# 1050a.net
KiCad netlist of a schematic drawn in Altium Designer
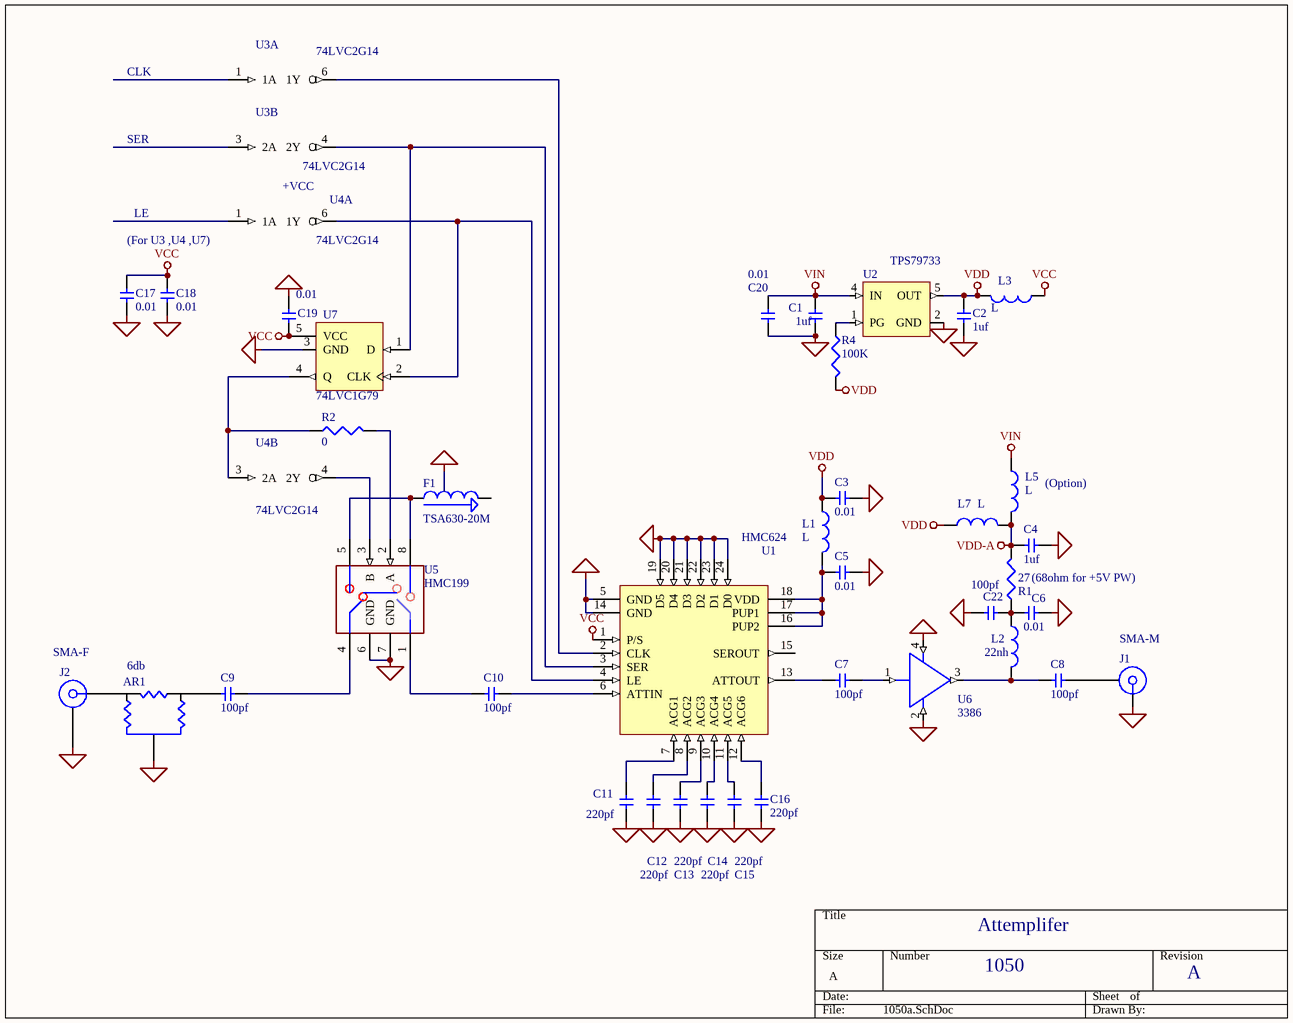
[diagram p0: 1050a.SchDoc]

(export (version "E")
  (design (tool "Eeschema 10.0.6"))
  (components
    (comp (ref "AR1") (value "6db") (libsource (lib "Project") (part "ATTN")))
    (comp (ref "C1") (value "1uf") (libsource (lib "Custom") (part "C")))
    (comp (ref "C2") (value "1uf") (libsource (lib "Custom") (part "C")))
    (comp (ref "C3") (value "0.01") (libsource (lib "Custom") (part "C")))
    (comp (ref "C4") (value "1uf") (libsource (lib "Custom") (part "C")))
    (comp (ref "C5") (value "0.01") (libsource (lib "Custom") (part "C")))
    (comp (ref "C6") (value "0.01") (libsource (lib "Custom") (part "C")))
    (comp (ref "C7") (value "100pf") (libsource (lib "Custom") (part "C")))
    (comp (ref "C8") (value "100pf") (libsource (lib "Custom") (part "C")))
    (comp (ref "C9") (value "100pf") (libsource (lib "Custom") (part "C")))
    (comp (ref "C10") (value "100pf") (libsource (lib "Custom") (part "C")))
    (comp (ref "C11") (value "220pf") (libsource (lib "Custom") (part "C")))
    (comp (ref "C12") (value "220pf") (libsource (lib "Custom") (part "C")))
    (comp (ref "C13") (value "220pf") (libsource (lib "Custom") (part "C")))
    (comp (ref "C14") (value "220pf") (libsource (lib "Custom") (part "C")))
    (comp (ref "C15") (value "220pf") (libsource (lib "Custom") (part "C")))
    (comp (ref "C16") (value "220pf") (libsource (lib "Custom") (part "C")))
    (comp (ref "C17") (value "0.01") (libsource (lib "Custom") (part "C")))
    (comp (ref "C18") (value "0.01") (libsource (lib "Custom") (part "C")))
    (comp (ref "C19") (value "0.01") (libsource (lib "Custom") (part "C")))
    (comp (ref "C20") (value "0.01") (libsource (lib "Custom") (part "C")))
    (comp (ref "C22") (value "100pf") (libsource (lib "Custom") (part "C")))
    (comp (ref "F1") (value "TSA630-20M") (libsource (lib "DDEVICE") (part "INDUCTOR VAR")))
    (comp (ref "J1") (value "SMA-M") (libsource (lib "DDEVICE") (part "BNC")))
    (comp (ref "J2") (value "SMA-F") (libsource (lib "DDEVICE") (part "BNC")))
    (comp (ref "L1") (value "L") (description "Chip Inductors") (libsource (lib "Custom") (part "L")))
    (comp (ref "L2") (value "22nh") (description "Chip Inductors") (libsource (lib "Custom") (part "L")))
    (comp (ref "L3")
      (value "L")
      (footprint "1008HS")
      (description "Chip Inductors")
      (libsource (lib "Custom") (part "L"))
    )
    (comp (ref "L5")
      (value "L")
      (footprint "1008HS")
      (description "Chip Inductors")
      (libsource (lib "Custom") (part "L"))
    )
    (comp (ref "L7")
      (value "L")
      (footprint "1008HS")
      (description "Chip Inductors")
      (libsource (lib "Custom") (part "L"))
    )
    (comp (ref "R1") (value "27") (libsource (lib "DDEVICE") (part "R")))
    (comp (ref "R2") (value "0") (libsource (lib "DDEVICE") (part "R")))
    (comp (ref "R4") (value "100K") (libsource (lib "DDEVICE") (part "R")))
    (comp (ref "U1") (value "HMC624") (libsource (lib "HITTICE") (part "HMC624")))
    (comp (ref "U2") (value "TPS79733") (libsource (lib "Project") (part "tps79733")))
    (comp (ref "U3") (value "74LVC2G14") (libsource (lib "FAIRCHILD") (part "74LVC2G14")))
    (comp (ref "U4") (value "74LVC2G14") (libsource (lib "FAIRCHILD") (part "74LVC2G14")))
    (comp (ref "U5") (value "HMC199") (libsource (lib "HITTICE") (part "hmc199")))
    (comp (ref "U6") (value "3386") (libsource (lib "Project") (part "MAR-4")))
    (comp (ref "U7") (value "74LVC1G79") (libsource (lib "TI Logic Flip-Flop") (part "74LVC1G79")))
  )
  (nets
    (net (code "1") (name "GND") (class "Default")
      (node (ref "AR1") (pin "2") (pinfunction "2_2") (pintype "passive"))
      (node (ref "C1") (pin "2") (pinfunction "2_2") (pintype "passive"))
      (node (ref "C11") (pin "2") (pinfunction "2_2") (pintype "passive"))
      (node (ref "C12") (pin "2") (pinfunction "2_2") (pintype "passive"))
      (node (ref "C13") (pin "2") (pinfunction "2_2") (pintype "passive"))
      (node (ref "C14") (pin "2") (pinfunction "2_2") (pintype "passive"))
      (node (ref "C15") (pin "2") (pinfunction "2_2") (pintype "passive"))
      (node (ref "C16") (pin "2") (pinfunction "2_2") (pintype "passive"))
      (node (ref "C17") (pin "1") (pinfunction "1_1") (pintype "passive"))
      (node (ref "C18") (pin "2") (pinfunction "2_2") (pintype "passive"))
      (node (ref "C19") (pin "2") (pinfunction "2_2") (pintype "passive"))
      (node (ref "C2") (pin "2") (pinfunction "2_2") (pintype "passive"))
      (node (ref "C20") (pin "2") (pinfunction "2_2") (pintype "passive"))
      (node (ref "C22") (pin "2") (pinfunction "2_2") (pintype "passive"))
      (node (ref "C3") (pin "2") (pinfunction "2_2") (pintype "passive"))
      (node (ref "C4") (pin "2") (pinfunction "2_2") (pintype "passive"))
      (node (ref "C5") (pin "2") (pinfunction "2_2") (pintype "passive"))
      (node (ref "C6") (pin "2") (pinfunction "2_2") (pintype "passive"))
      (node (ref "J1") (pin "1") (pinfunction "1_1") (pintype "passive"))
      (node (ref "J2") (pin "2") (pinfunction "2_2") (pintype "passive"))
      (node (ref "U1") (pin "14") (pinfunction "GND_14") (pintype "power_in"))
      (node (ref "U1") (pin "19") (pinfunction "D5_19") (pintype "input"))
      (node (ref "U1") (pin "20") (pinfunction "D4_20") (pintype "input"))
      (node (ref "U1") (pin "21") (pinfunction "D3_21") (pintype "input"))
      (node (ref "U1") (pin "22") (pinfunction "D2_22") (pintype "input"))
      (node (ref "U1") (pin "23") (pinfunction "D1_23") (pintype "input"))
      (node (ref "U1") (pin "24") (pinfunction "D0_24") (pintype "input"))
      (node (ref "U1") (pin "5") (pinfunction "GND_5") (pintype "power_in"))
      (node (ref "U2") (pin "2") (pinfunction "GND_2") (pintype "power_in"))
      (node (ref "U3") (pin "2") (pinfunction "GND_2") (pintype "power_in"))
      (node (ref "U4") (pin "2") (pinfunction "GND_2") (pintype "power_in"))
      (node (ref "U5") (pin "6") (pinfunction "GND_6") (pintype "passive"))
      (node (ref "U5") (pin "7") (pinfunction "GND_7") (pintype "power_in"))
      (node (ref "U6") (pin "2") (pintype "input"))
      (node (ref "U6") (pin "4") (pintype "input"))
      (node (ref "U7") (pin "3") (pinfunction "GND_3") (pintype "power_in"))
    )
    (net (code "2") (name "Net-(AR1-Pad1)") (class "Default")
      (node (ref "AR1") (pin "1") (pinfunction "1_1") (pintype "passive"))
      (node (ref "J2") (pin "1") (pinfunction "1_1") (pintype "passive"))
    )
    (net (code "3") (name "Net-(AR1-Pad3)") (class "Default")
      (node (ref "AR1") (pin "3") (pinfunction "3_3") (pintype "passive"))
      (node (ref "C9") (pin "1") (pinfunction "1_1") (pintype "passive"))
    )
    (net (code "4") (name "Net-(C8-Pad2)") (class "Default")
      (node (ref "C8") (pin "2") (pinfunction "2_2") (pintype "passive"))
      (node (ref "J1") (pin "2") (pinfunction "2_2") (pintype "passive"))
    )
    (net (code "5") (name "Net-(C22-Pad1)") (class "Default")
      (node (ref "C22") (pin "1") (pinfunction "1_1") (pintype "passive"))
      (node (ref "C6") (pin "1") (pinfunction "1_1") (pintype "passive"))
      (node (ref "L2") (pin "1") (pinfunction "1_1") (pintype "passive"))
      (node (ref "R1") (pin "1") (pinfunction "1_1") (pintype "passive"))
    )
    (net (code "6") (name "Net-(U1-ACG1)") (class "Default")
      (node (ref "C11") (pin "1") (pinfunction "1_1") (pintype "passive"))
      (node (ref "U1") (pin "7") (pinfunction "ACG1_7") (pintype "input"))
    )
    (net (code "7") (name "Net-(U1-ACG2)") (class "Default")
      (node (ref "C12") (pin "1") (pinfunction "1_1") (pintype "passive"))
      (node (ref "U1") (pin "8") (pinfunction "ACG2_8") (pintype "input"))
    )
    (net (code "8") (name "Net-(U1-ACG3)") (class "Default")
      (node (ref "C13") (pin "1") (pinfunction "1_1") (pintype "passive"))
      (node (ref "U1") (pin "9") (pinfunction "ACG3_9") (pintype "input"))
    )
    (net (code "9") (name "Net-(U1-ACG4)") (class "Default")
      (node (ref "C14") (pin "1") (pinfunction "1_1") (pintype "passive"))
      (node (ref "U1") (pin "10") (pinfunction "ACG4_10") (pintype "input"))
    )
    (net (code "10") (name "Net-(U1-ACG5)") (class "Default")
      (node (ref "C15") (pin "1") (pinfunction "1_1") (pintype "passive"))
      (node (ref "U1") (pin "11") (pinfunction "ACG5_11") (pintype "input"))
    )
    (net (code "11") (name "Net-(U1-ACG6)") (class "Default")
      (node (ref "C16") (pin "1") (pinfunction "1_1") (pintype "passive"))
      (node (ref "U1") (pin "12") (pinfunction "ACG6_12") (pintype "input"))
    )
    (net (code "12") (name "Net-(U1-ATTIN)") (class "Default")
      (node (ref "C10") (pin "2") (pinfunction "2_2") (pintype "passive"))
      (node (ref "U1") (pin "6") (pinfunction "ATTIN_6") (pintype "input"))
    )
    (net (code "13") (name "Net-(U1-ATTOUT)") (class "Default")
      (node (ref "C7") (pin "1") (pinfunction "1_1") (pintype "passive"))
      (node (ref "U1") (pin "13") (pinfunction "ATTOUT_13") (pintype "output"))
    )
    (net (code "14") (name "Net-(U1-CLK)") (class "Default")
      (node (ref "U1") (pin "2") (pinfunction "CLK_2") (pintype "input"))
      (node (ref "U3") (pin "6") (pinfunction "1Y_6") (pintype "output"))
    )
    (net (code "15") (name "Net-(U1-LE)") (class "Default")
      (node (ref "U1") (pin "4") (pinfunction "LE_4") (pintype "input"))
      (node (ref "U4") (pin "6") (pinfunction "1Y_6") (pintype "output"))
      (node (ref "U7") (pin "2") (pinfunction "CLK_2") (pintype "input"))
    )
    (net (code "16") (name "Net-(U1-PUP1)") (class "Default")
      (node (ref "C5") (pin "1") (pinfunction "1_1") (pintype "passive"))
      (node (ref "L1") (pin "2") (pinfunction "2_2") (pintype "passive"))
      (node (ref "U1") (pin "16") (pinfunction "PUP2_16") (pintype "passive"))
      (node (ref "U1") (pin "17") (pinfunction "PUP1_17") (pintype "passive"))
      (node (ref "U1") (pin "18") (pinfunction "VDD_18") (pintype "power_in"))
    )
    (net (code "17") (name "Net-(U1-SER)") (class "Default")
      (node (ref "U1") (pin "3") (pinfunction "SER_3") (pintype "input"))
      (node (ref "U3") (pin "4") (pinfunction "2Y_4") (pintype "output"))
      (node (ref "U7") (pin "1") (pinfunction "D_1") (pintype "input"))
    )
    (net (code "18") (name "Net-(U2-PG)") (class "Default")
      (node (ref "R4") (pin "1") (pinfunction "1_1") (pintype "passive"))
      (node (ref "U2") (pin "1") (pinfunction "PG_1") (pintype "input"))
    )
    (net (code "19") (name "Net-(U4B-2A)") (class "Default")
      (node (ref "R2") (pin "1") (pinfunction "1_1") (pintype "passive"))
      (node (ref "U4") (pin "3") (pinfunction "2A_3") (pintype "input"))
      (node (ref "U7") (pin "4") (pinfunction "Q_4") (pintype "output"))
    )
    (net (code "20") (name "Net-(U4B-2Y)") (class "Default")
      (node (ref "U4") (pin "4") (pinfunction "2Y_4") (pintype "output"))
      (node (ref "U5") (pin "3") (pinfunction "B_3") (pintype "input"))
    )
    (net (code "21") (name "Net-(U5-A)") (class "Default")
      (node (ref "R2") (pin "2") (pinfunction "2_2") (pintype "passive"))
      (node (ref "U5") (pin "2") (pinfunction "A_2") (pintype "input"))
    )
    (net (code "22") (name "Net-(U5-RF1)") (class "Default")
      (node (ref "F1") (pin "2") (pinfunction "2_2") (pintype "passive"))
      (node (ref "U5") (pin "5") (pinfunction "RF2_5") (pintype "passive"))
      (node (ref "U5") (pin "8") (pinfunction "RF1_8") (pintype "passive"))
    )
    (net (code "23") (name "Net-(U5-RFC1)") (class "Default")
      (node (ref "C10") (pin "1") (pinfunction "1_1") (pintype "passive"))
      (node (ref "U5") (pin "1") (pinfunction "RFC1_1") (pintype "passive"))
    )
    (net (code "24") (name "Net-(U5-RFC2)") (class "Default")
      (node (ref "C9") (pin "2") (pinfunction "2_2") (pintype "passive"))
      (node (ref "U5") (pin "4") (pinfunction "RFC2_4") (pintype "passive"))
    )
    (net (code "25") (name "Net-(U6-IN)") (class "Default")
      (node (ref "C7") (pin "2") (pinfunction "2_2") (pintype "passive"))
      (node (ref "U6") (pin "1") (pinfunction "IN_1") (pintype "input"))
    )
    (net (code "26") (name "Net-(U6-OUT])") (class "Default")
      (node (ref "C8") (pin "1") (pinfunction "1_1") (pintype "passive"))
      (node (ref "L2") (pin "2") (pinfunction "2_2") (pintype "passive"))
      (node (ref "U6") (pin "3") (pinfunction "OUT]_3") (pintype "output"))
    )
    (net (code "27") (name "VCC") (class "Default")
      (node (ref "C17") (pin "2") (pinfunction "2_2") (pintype "passive"))
      (node (ref "C18") (pin "1") (pinfunction "1_1") (pintype "passive"))
      (node (ref "C19") (pin "1") (pinfunction "1_1") (pintype "passive"))
      (node (ref "L3") (pin "1") (pinfunction "1_1") (pintype "passive"))
      (node (ref "U1") (pin "1") (pinfunction "P/S_1") (pintype "input"))
      (node (ref "U3") (pin "5") (pinfunction "VCC_5") (pintype "power_in"))
      (node (ref "U4") (pin "5") (pinfunction "VCC_5") (pintype "power_in"))
      (node (ref "U7") (pin "5") (pinfunction "VCC_5") (pintype "power_in"))
    )
    (net (code "28") (name "VDD") (class "Default")
      (node (ref "C2") (pin "1") (pinfunction "1_1") (pintype "passive"))
      (node (ref "C3") (pin "1") (pinfunction "1_1") (pintype "passive"))
      (node (ref "L1") (pin "1") (pinfunction "1_1") (pintype "passive"))
      (node (ref "L3") (pin "2") (pinfunction "2_2") (pintype "passive"))
      (node (ref "L7") (pin "1") (pinfunction "1_1") (pintype "passive"))
      (node (ref "R4") (pin "2") (pinfunction "2_2") (pintype "passive"))
      (node (ref "U2") (pin "5") (pinfunction "OUT_5") (pintype "output"))
    )
    (net (code "29") (name "VDD-A") (class "Default")
      (node (ref "C4") (pin "1") (pinfunction "1_1") (pintype "passive"))
      (node (ref "L5") (pin "2") (pinfunction "2_2") (pintype "passive"))
      (node (ref "L7") (pin "2") (pinfunction "2_2") (pintype "passive"))
      (node (ref "R1") (pin "2") (pinfunction "2_2") (pintype "passive"))
    )
    (net (code "30") (name "VIN") (class "Default")
      (node (ref "C1") (pin "1") (pinfunction "1_1") (pintype "passive"))
      (node (ref "C20") (pin "1") (pinfunction "1_1") (pintype "passive"))
      (node (ref "L5") (pin "1") (pinfunction "1_1") (pintype "passive"))
      (node (ref "U2") (pin "4") (pinfunction "IN_4") (pintype "input"))
    )
    (net (code "31") (name "unconnected-(F1-Pad1)") (class "Default")
      (node (ref "F1") (pin "1") (pinfunction "1_1") (pintype "passive"))
    )
    (net (code "32") (name "unconnected-(U1-SEROUT-Pad15)") (class "Default")
      (node (ref "U1") (pin "15") (pinfunction "SEROUT_15") (pintype "output"))
    )
    (net (code "33") (name "unconnected-(U3A-1A-Pad1)") (class "Default")
      (node (ref "U3") (pin "1") (pinfunction "1A_1") (pintype "input"))
    )
    (net (code "34") (name "unconnected-(U3B-2A-Pad3)") (class "Default")
      (node (ref "U3") (pin "3") (pinfunction "2A_3") (pintype "input"))
    )
    (net (code "35") (name "unconnected-(U4A-1A-Pad1)") (class "Default")
      (node (ref "U4") (pin "1") (pinfunction "1A_1") (pintype "input"))
    )
  )
)
